# v2.net
KiCad netlist of a schematic drawn in EAGLE
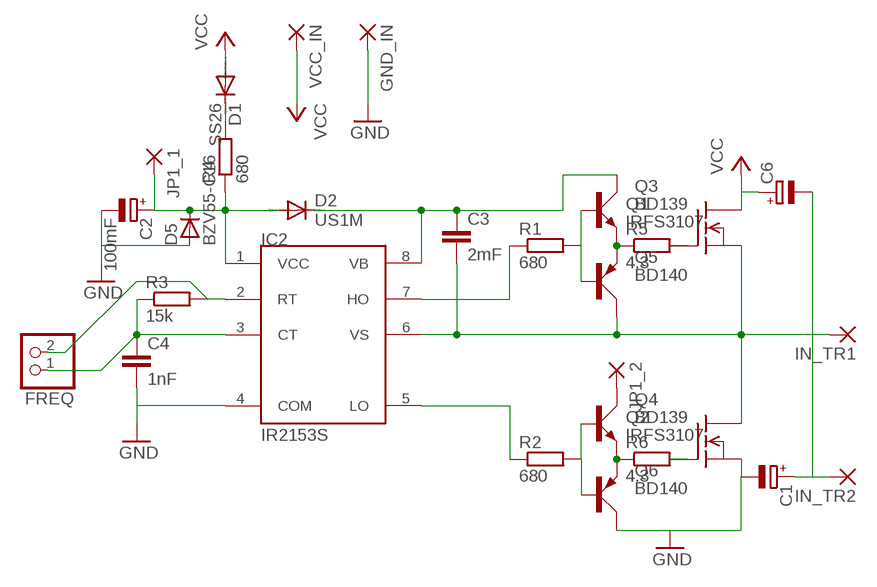
[diagram p0: schematic, sheet 1]

(export (version "E")
  (design (tool "Eeschema 10.0.6"))
  (components
    (comp (ref "C1")
      (value "CPOL-EUE10-22.5")
      (footprint "eagle-import:EB22,5D")
      (libsource (lib "eagle-import") (part "CPOL-EUE10-22.5"))
    )
    (comp (ref "C2")
      (value "100mF")
      (footprint "eagle-import:E5-10,5")
      (libsource (lib "eagle-import") (part "CPOL-EUE5-10.5"))
    )
    (comp (ref "C3")
      (value "2mF")
      (footprint "eagle-import:C0805")
      (libsource (lib "eagle-import") (part "C-EUC0805"))
    )
    (comp (ref "C4")
      (value "1nF")
      (footprint "eagle-import:C0805")
      (libsource (lib "eagle-import") (part "C-EUC0805"))
    )
    (comp (ref "C6")
      (value "CPOL-EUE10-22.5")
      (footprint "eagle-import:EB22,5D")
      (libsource (lib "eagle-import") (part "CPOL-EUE10-22.5"))
    )
    (comp (ref "D1")
      (value "SS26")
      (footprint "eagle-import:DO-214AC")
      (libsource (lib "eagle-import") (part "DIODE-DO-214AC"))
    )
    (comp (ref "D2")
      (value "US1M")
      (footprint "eagle-import:DO-214AC")
      (libsource (lib "eagle-import") (part "DIODE-DO-214AC"))
    )
    (comp (ref "D5")
      (value "BZV55-C16")
      (footprint "eagle-import:SOD80")
      (libsource (lib "eagle-import") (part "D-SOD-80"))
    )
    (comp (ref "FREQ")
      (value "PINHD-1X2/90")
      (footprint "eagle-import:1X02_90")
      (libsource (lib "eagle-import") (part "PINHD-1X2/90"))
    )
    (comp (ref "GND_IN")
      (value "SMD5")
      (footprint "eagle-import:SMD2,54-5,08")
      (libsource (lib "eagle-import") (part "SMD5"))
    )
    (comp (ref "IC2")
      (value "IR2153S")
      (footprint "eagle-import:SO08")
      (libsource (lib "eagle-import") (part "IR2153S"))
    )
    (comp (ref "IN_TR1")
      (value "SMD5")
      (footprint "eagle-import:SMD2,54-5,08")
      (libsource (lib "eagle-import") (part "SMD5"))
    )
    (comp (ref "IN_TR2")
      (value "SMD5")
      (footprint "eagle-import:SMD2,54-5,08")
      (libsource (lib "eagle-import") (part "SMD5"))
    )
    (comp (ref "JP1_1")
      (value "1,6/0,8")
      (footprint "eagle-import:1,6_0,8")
      (libsource (lib "eagle-import") (part "1,6/0,8"))
    )
    (comp (ref "JP1_2")
      (value "1,6/0,8")
      (footprint "eagle-import:1,6_0,8")
      (libsource (lib "eagle-import") (part "1,6/0,8"))
    )
    (comp (ref "Q1")
      (value "IRFS3107")
      (footprint "eagle-import:D2PAK")
      (libsource (lib "eagle-import") (part "IRF510D2PAK"))
    )
    (comp (ref "Q2")
      (value "IRFS3107")
      (footprint "eagle-import:D2PAK")
      (libsource (lib "eagle-import") (part "IRF510D2PAK"))
    )
    (comp (ref "Q3")
      (value "BD139")
      (footprint "eagle-import:TO126AV")
      (libsource (lib "eagle-import") (part "BD139"))
    )
    (comp (ref "Q4")
      (value "BD139")
      (footprint "eagle-import:TO126AV")
      (libsource (lib "eagle-import") (part "BD139"))
    )
    (comp (ref "Q5")
      (value "BD140")
      (footprint "eagle-import:TO126AV")
      (libsource (lib "eagle-import") (part "BD140"))
    )
    (comp (ref "Q6")
      (value "BD140")
      (footprint "eagle-import:TO126AV")
      (libsource (lib "eagle-import") (part "BD140"))
    )
    (comp (ref "R1")
      (value "680")
      (footprint "eagle-import:R0805")
      (libsource (lib "eagle-import") (part "R-EU_R0805"))
    )
    (comp (ref "R2")
      (value "680")
      (footprint "eagle-import:R0805")
      (libsource (lib "eagle-import") (part "R-EU_R0805"))
    )
    (comp (ref "R3")
      (value "15k")
      (footprint "eagle-import:R0805")
      (libsource (lib "eagle-import") (part "R-EU_R0805"))
    )
    (comp (ref "R4")
      (value "680")
      (footprint "eagle-import:R0805")
      (libsource (lib "eagle-import") (part "R-EU_R0805"))
    )
    (comp (ref "R5")
      (value "4.3")
      (footprint "eagle-import:R0805")
      (libsource (lib "eagle-import") (part "R-EU_R0805"))
    )
    (comp (ref "R6")
      (value "4.3")
      (footprint "eagle-import:R0805")
      (libsource (lib "eagle-import") (part "R-EU_R0805"))
    )
    (comp (ref "VCC_IN")
      (value "SMD5")
      (footprint "eagle-import:SMD2,54-5,08")
      (libsource (lib "eagle-import") (part "SMD5"))
    )
  )
  (nets
    (net (code "1") (name "GND") (class "Default")
      (node (ref "C1") (pin "-") (pinfunction "-_-") (pintype "passive"))
      (node (ref "C2") (pin "-") (pinfunction "-_-") (pintype "passive"))
      (node (ref "C4") (pin "2") (pinfunction "2_2") (pintype "passive"))
      (node (ref "D5") (pin "2") (pinfunction "A_2") (pintype "passive"))
      (node (ref "GND_IN") (pin "1") (pinfunction "P_1") (pintype "passive"))
      (node (ref "IC2") (pin "4") (pinfunction "COM_4") (pintype "power_in"))
      (node (ref "Q2") (pin "3") (pinfunction "S_3") (pintype "passive"))
      (node (ref "Q6") (pin "C") (pinfunction "C_C") (pintype "passive"))
    )
    (net (code "2") (name "Net-(D1-PadC)") (class "Default")
      (node (ref "D1") (pin "C") (pinfunction "C_C") (pintype "passive"))
      (node (ref "R4") (pin "2") (pinfunction "2_2") (pintype "passive"))
    )
    (net (code "3") (name "Net-(D5-C)") (class "Default")
      (node (ref "C2") (pin "+") (pinfunction "+_+") (pintype "passive"))
      (node (ref "D2") (pin "A") (pinfunction "A_A") (pintype "passive"))
      (node (ref "D5") (pin "1") (pinfunction "C_1") (pintype "passive"))
      (node (ref "IC2") (pin "1") (pinfunction "VCC_1") (pintype "power_in"))
      (node (ref "JP1_1") (pin "1") (pinfunction "P_1") (pintype "passive"))
      (node (ref "R4") (pin "1") (pinfunction "1_1") (pintype "passive"))
    )
    (net (code "4") (name "Net-(IC2-CT)") (class "Default")
      (node (ref "C4") (pin "1") (pinfunction "1_1") (pintype "passive"))
      (node (ref "FREQ") (pin "1") (pinfunction "1_1") (pintype "passive"))
      (node (ref "IC2") (pin "3") (pinfunction "CT_3") (pintype "input"))
      (node (ref "R3") (pin "1") (pinfunction "1_1") (pintype "passive"))
    )
    (net (code "5") (name "Net-(IC2-HO)") (class "Default")
      (node (ref "IC2") (pin "7") (pinfunction "HO_7") (pintype "output"))
      (node (ref "R1") (pin "1") (pinfunction "1_1") (pintype "passive"))
    )
    (net (code "6") (name "Net-(IC2-LO)") (class "Default")
      (node (ref "IC2") (pin "5") (pinfunction "LO_5") (pintype "output"))
      (node (ref "R2") (pin "1") (pinfunction "1_1") (pintype "passive"))
    )
    (net (code "7") (name "Net-(IC2-RT)") (class "Default")
      (node (ref "FREQ") (pin "2") (pinfunction "2_2") (pintype "passive"))
      (node (ref "IC2") (pin "2") (pinfunction "RT_2") (pintype "output"))
      (node (ref "R3") (pin "2") (pinfunction "2_2") (pintype "passive"))
    )
    (net (code "8") (name "Net-(IC2-VB)") (class "Default")
      (node (ref "C3") (pin "1") (pinfunction "1_1") (pintype "passive"))
      (node (ref "D2") (pin "C") (pinfunction "C_C") (pintype "passive"))
      (node (ref "IC2") (pin "8") (pinfunction "VB_8") (pintype "power_in"))
      (node (ref "Q3") (pin "C") (pinfunction "C_C") (pintype "passive"))
    )
    (net (code "9") (name "Net-(IC2-VS)") (class "Default")
      (node (ref "C3") (pin "2") (pinfunction "2_2") (pintype "passive"))
      (node (ref "IC2") (pin "6") (pinfunction "VS_6") (pintype "power_in"))
      (node (ref "IN_TR1") (pin "1") (pinfunction "P_1") (pintype "passive"))
      (node (ref "Q1") (pin "3") (pinfunction "S_3") (pintype "passive"))
      (node (ref "Q2") (pin "2") (pinfunction "D_2") (pintype "passive"))
      (node (ref "Q5") (pin "C") (pinfunction "C_C") (pintype "passive"))
    )
    (net (code "10") (name "Net-(IN_TR2-P)") (class "Default")
      (node (ref "C1") (pin "+") (pinfunction "+_+") (pintype "passive"))
      (node (ref "C6") (pin "-") (pinfunction "-_-") (pintype "passive"))
      (node (ref "IN_TR2") (pin "1") (pinfunction "P_1") (pintype "passive"))
    )
    (net (code "11") (name "Net-(JP1_2-P)") (class "Default")
      (node (ref "JP1_2") (pin "1") (pinfunction "P_1") (pintype "passive"))
      (node (ref "Q4") (pin "C") (pinfunction "C_C") (pintype "passive"))
    )
    (net (code "12") (name "Net-(Q1-G)") (class "Default")
      (node (ref "Q1") (pin "1") (pinfunction "G_1") (pintype "passive"))
      (node (ref "R5") (pin "2") (pinfunction "2_2") (pintype "passive"))
    )
    (net (code "13") (name "Net-(Q2-G)") (class "Default")
      (node (ref "Q2") (pin "1") (pinfunction "G_1") (pintype "passive"))
      (node (ref "R6") (pin "2") (pinfunction "2_2") (pintype "passive"))
    )
    (net (code "14") (name "Net-(Q3-PadB)") (class "Default")
      (node (ref "Q3") (pin "B") (pinfunction "B_B") (pintype "passive"))
      (node (ref "Q5") (pin "B") (pinfunction "B_B") (pintype "passive"))
      (node (ref "R1") (pin "2") (pinfunction "2_2") (pintype "passive"))
    )
    (net (code "15") (name "Net-(Q3-PadE)") (class "Default")
      (node (ref "Q3") (pin "E") (pinfunction "E_E") (pintype "passive"))
      (node (ref "Q5") (pin "E") (pinfunction "E_E") (pintype "passive"))
      (node (ref "R5") (pin "1") (pinfunction "1_1") (pintype "passive"))
    )
    (net (code "16") (name "Net-(Q4-PadB)") (class "Default")
      (node (ref "Q4") (pin "B") (pinfunction "B_B") (pintype "passive"))
      (node (ref "Q6") (pin "B") (pinfunction "B_B") (pintype "passive"))
      (node (ref "R2") (pin "2") (pinfunction "2_2") (pintype "passive"))
    )
    (net (code "17") (name "Net-(Q4-PadE)") (class "Default")
      (node (ref "Q4") (pin "E") (pinfunction "E_E") (pintype "passive"))
      (node (ref "Q6") (pin "E") (pinfunction "E_E") (pintype "passive"))
      (node (ref "R6") (pin "1") (pinfunction "1_1") (pintype "passive"))
    )
    (net (code "18") (name "VCC") (class "Default")
      (node (ref "C6") (pin "+") (pinfunction "+_+") (pintype "passive"))
      (node (ref "D1") (pin "A") (pinfunction "A_A") (pintype "passive"))
      (node (ref "Q1") (pin "2") (pinfunction "D_2") (pintype "passive"))
      (node (ref "VCC_IN") (pin "1") (pinfunction "P_1") (pintype "passive"))
    )
  )
)
